# voeding.net
KiCad netlist of a schematic drawn in Altium Designer
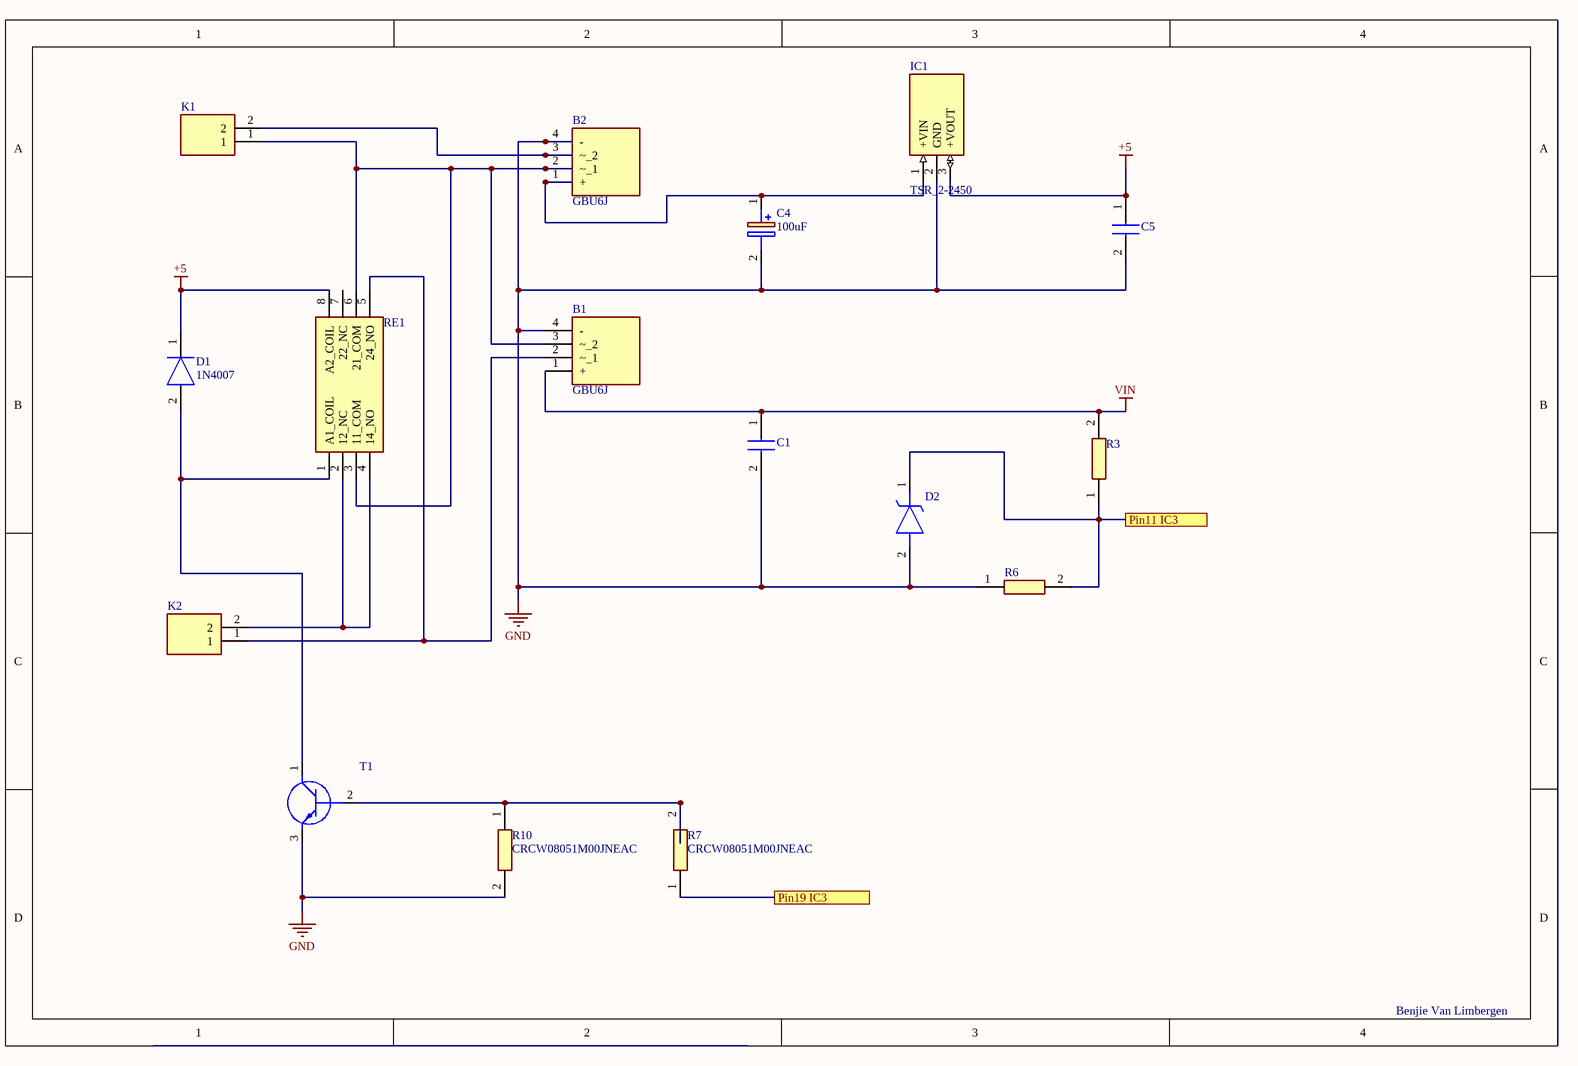
[diagram p0: voeding.SchDoc]

(export (version "E")
  (design (tool "Eeschema 10.0.6"))
  (components
    (comp (ref "B1")
      (value "GBU6J")
      (footprint "SamacSys:GBU6J")
      (description "Bridge Rectifier")
      (libsource (lib "*") (part "GBU6J"))
    )
    (comp (ref "B2")
      (value "GBU6J")
      (footprint "SamacSys:GBU6J")
      (description "Bridge Rectifier")
      (libsource (lib "*") (part "GBU6J"))
    )
    (comp (ref "C1")
      (value "860010683032")
      (footprint "SamacSys:CAPPRD1000W80D2200H4100")
      (description "Capacitor C1 4700u 50v")
      (libsource (lib "*") (part "860010683032"))
    )
    (comp (ref "C4")
      (value "100uF")
      (footprint "SamacSys:CAPPRD200W55D500H1200")
      (description "Capacitor Polarised C4")
      (fields (field (name "MANUFACTURER_PART_NUMBER") "ECA-1HHG2R2B"))
      (libsource (lib "*") (part "ECA-1HHG2R2B"))
    )
    (comp (ref "C5")
      (value "860010683032")
      (footprint "SamacSys:CAPPRD200W52D500H1250")
      (description "Capacitor C5")
      (libsource (lib "*") (part "860010683032"))
    )
    (comp (ref "D1")
      (value "1N4007")
      (footprint "SamacSys:DIOAD1410W86L470D235")
      (description "Diode D1")
      (libsource (lib "*") (part "1N4007"))
    )
    (comp (ref "D2")
      (value "1N5231BTR")
      (footprint "SamacSys:DIOAD1068W53L380D172")
      (description "Zener Diode D2")
      (libsource (lib "*") (part "1N5231BTR"))
    )
    (comp (ref "IC1")
      (value "TSR_2-2450")
      (footprint "SamacSys:TSR-2")
      (description "Power Supply IC1")
      (fields
        (field (name "MOUSER2 PART NUMBER") "495-TSR2-2450")
        (field (name "MANUFACTURER_PART_NUMBER") "TSR 2-2450")
      )
      (libsource (lib "*") (part "TSR_2-2450"))
    )
    (comp (ref "K1")
      (value "691214110002")
      (footprint "SamacSys:691214110002")
      (description "Connector")
      (libsource (lib "*") (part "691214110002"))
    )
    (comp (ref "K2")
      (value "691214110002")
      (footprint "SamacSys:691214110002")
      (description "Connector")
      (libsource (lib "*") (part "691214110002"))
    )
    (comp (ref "R3")
      (value "CRCW08051M00JNEAC")
      (footprint "SamacSys:RESC2012X60N")
      (description "Resistor R1-22")
      (fields (field (name "MOUSER2 PART NUMBER") "71-CRCW08051M00JNEAC"))
      (libsource (lib "") (part "CRCW08051M00JNEAC_1"))
    )
    (comp (ref "R6")
      (value "CRCW08051M00JNEAC")
      (footprint "SamacSys:RESC2012X60N")
      (description "Resistor R1-22")
      (fields (field (name "MOUSER2 PART NUMBER") "71-CRCW08051M00JNEAC"))
      (libsource (lib "") (part "CRCW08051M00JNEAC_2"))
    )
    (comp (ref "R7")
      (value "CRCW08051M00JNEAC")
      (footprint "SamacSys:RESC2012X60N")
      (description "Resistor R1-22")
      (fields (field (name "MOUSER2 PART NUMBER") "71-CRCW08051M00JNEAC"))
      (libsource (lib "") (part "CRCW08051M00JNEAC_1"))
    )
    (comp (ref "R10")
      (value "CRCW08051M00JNEAC")
      (footprint "SamacSys:RESC2012X60N")
      (description "Resistor R1-22")
      (fields (field (name "MOUSER2 PART NUMBER") "71-CRCW08051M00JNEAC"))
      (libsource (lib "SamacSys") (part "CRCW08051M00JNEAC"))
    )
    (comp (ref "RE1")
      (value "RT424005")
      (footprint "SamacSys:RT42")
      (description "Relay or Contactor")
      (fields (field (name "MOUSER2 PART NUMBER") "655-RT424005"))
      (libsource (lib "*") (part "RT424005"))
    )
    (comp (ref "T1")
      (value "BC547CBU")
      (footprint "SamacSys:BC547CBU")
      (description "Transistor BJT NPN")
      (libsource (lib "*") (part "BC547CBU"))
    )
  )
  (nets
    (net (code "1") (name "+5") (class "Default")
      (node (ref "C5") (pin "1") (pinfunction "+_1") (pintype "power_in"))
      (node (ref "D1") (pin "1") (pinfunction "K_1") (pintype "passive"))
      (node (ref "IC1") (pin "3") (pinfunction "+VOUT_3") (pintype "bidirectional"))
      (node (ref "RE1") (pin "8") (pinfunction "A2_COIL_8") (pintype "passive"))
    )
    (net (code "2") (name "/Pin11 IC3") (class "Default")
      (node (ref "D2") (pin "1") (pinfunction "K_1") (pintype "passive"))
      (node (ref "R3") (pin "1") (pinfunction "1_1") (pintype "passive"))
      (node (ref "R6") (pin "2") (pinfunction "2_2") (pintype "passive"))
    )
    (net (code "3") (name "/Pin19 IC3") (class "Default")
      (node (ref "R7") (pin "1") (pinfunction "1_1") (pintype "passive"))
    )
    (net (code "4") (name "GND") (class "Default")
      (node (ref "B1") (pin "4") (pinfunction "-_4") (pintype "passive"))
      (node (ref "B2") (pin "4") (pinfunction "-_4") (pintype "passive"))
      (node (ref "C1") (pin "2") (pinfunction "-_2") (pintype "power_in"))
      (node (ref "C4") (pin "2") (pinfunction "-_2") (pintype "passive"))
      (node (ref "C5") (pin "2") (pinfunction "-_2") (pintype "power_in"))
      (node (ref "D2") (pin "2") (pinfunction "A_2") (pintype "passive"))
      (node (ref "IC1") (pin "2") (pinfunction "GND_2") (pintype "power_in"))
      (node (ref "R10") (pin "2") (pinfunction "2_2") (pintype "passive"))
      (node (ref "R6") (pin "1") (pinfunction "1_1") (pintype "passive"))
      (node (ref "T1") (pin "3") (pinfunction "E_3") (pintype "passive"))
    )
    (net (code "5") (name "Net-(B1-~_1)") (class "Default")
      (node (ref "B1") (pin "2") (pinfunction "~_1_2") (pintype "passive"))
      (node (ref "K2") (pin "1") (pinfunction "1_1") (pintype "passive"))
      (node (ref "RE1") (pin "5") (pinfunction "24_NO_5") (pintype "passive"))
    )
    (net (code "6") (name "Net-(B1-~_2)") (class "Default")
      (node (ref "B1") (pin "3") (pinfunction "~_2_3") (pintype "passive"))
      (node (ref "B2") (pin "2") (pinfunction "~_1_2") (pintype "passive"))
      (node (ref "K1") (pin "1") (pinfunction "1_1") (pintype "passive"))
      (node (ref "RE1") (pin "3") (pinfunction "11_COM_3") (pintype "passive"))
      (node (ref "RE1") (pin "6") (pinfunction "21_COM_6") (pintype "passive"))
    )
    (net (code "7") (name "Net-(B2-+)") (class "Default")
      (node (ref "B2") (pin "1") (pinfunction "+_1") (pintype "passive"))
      (node (ref "C4") (pin "1") (pinfunction "+_1") (pintype "passive"))
      (node (ref "IC1") (pin "1") (pinfunction "+VIN_1") (pintype "input"))
    )
    (net (code "8") (name "Net-(B2-~_2)") (class "Default")
      (node (ref "B2") (pin "3") (pinfunction "~_2_3") (pintype "passive"))
      (node (ref "K1") (pin "2") (pinfunction "2_2") (pintype "passive"))
    )
    (net (code "9") (name "Net-(D1-A)") (class "Default")
      (node (ref "D1") (pin "2") (pinfunction "A_2") (pintype "passive"))
      (node (ref "RE1") (pin "1") (pinfunction "A1_COIL_1") (pintype "passive"))
      (node (ref "T1") (pin "1") (pinfunction "C_1") (pintype "passive"))
    )
    (net (code "10") (name "Net-(RE1-12_NC)") (class "Default")
      (node (ref "K2") (pin "2") (pinfunction "2_2") (pintype "passive"))
      (node (ref "RE1") (pin "2") (pinfunction "12_NC_2") (pintype "passive"))
      (node (ref "RE1") (pin "4") (pinfunction "14_NO_4") (pintype "passive"))
    )
    (net (code "11") (name "Net-(T1-B)") (class "Default")
      (node (ref "R10") (pin "1") (pinfunction "1_1") (pintype "passive"))
      (node (ref "R7") (pin "2") (pinfunction "2_2") (pintype "passive"))
      (node (ref "T1") (pin "2") (pinfunction "B_2") (pintype "passive"))
    )
    (net (code "12") (name "VIN") (class "Default")
      (node (ref "B1") (pin "1") (pinfunction "+_1") (pintype "passive"))
      (node (ref "C1") (pin "1") (pinfunction "+_1") (pintype "power_in"))
      (node (ref "R3") (pin "2") (pinfunction "2_2") (pintype "passive"))
    )
    (net (code "13") (name "unconnected-(RE1-22_NC-Pad7)") (class "Default")
      (node (ref "RE1") (pin "7") (pinfunction "22_NC_7") (pintype "passive"))
    )
  )
)
